# Tracking_Bug.net
KiCad netlist of a schematic drawn in EAGLE
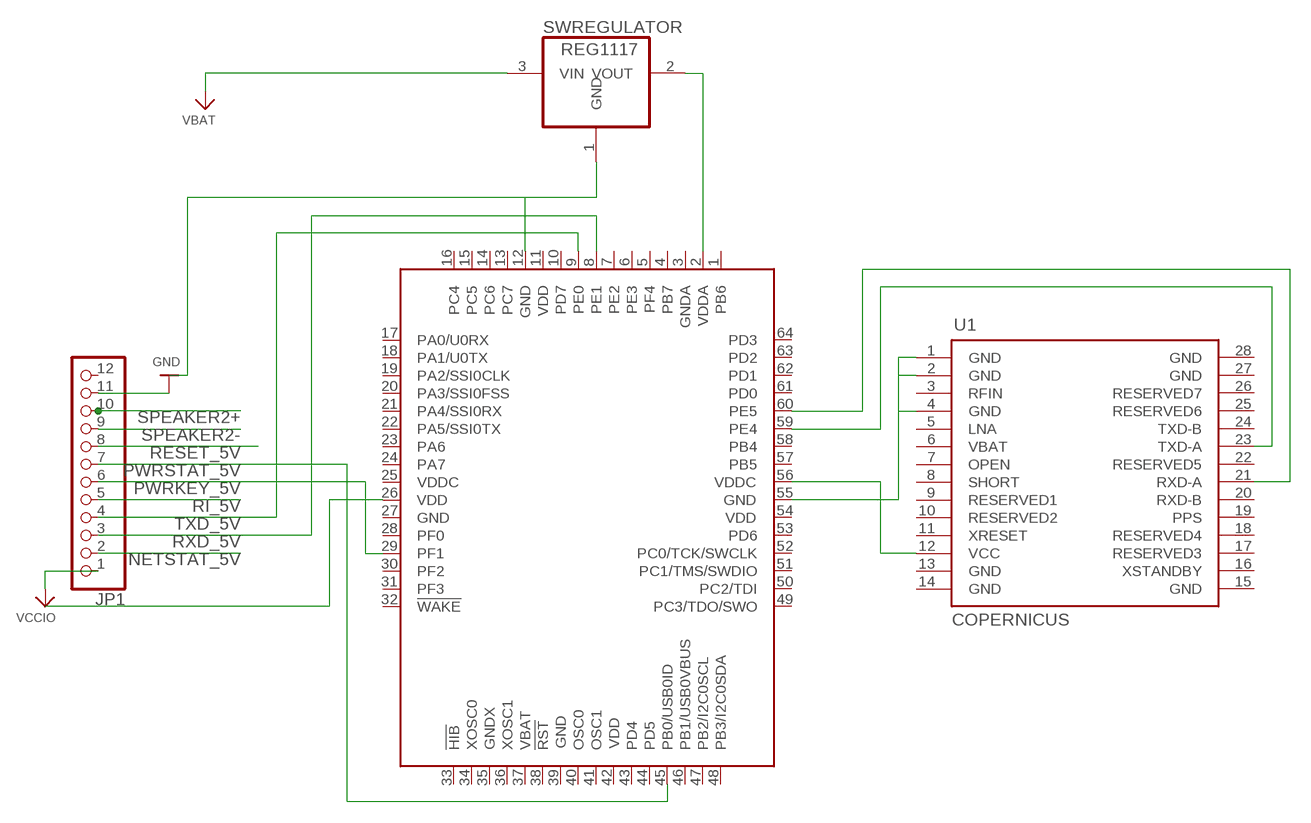
[diagram p0: schematic, sheet 1]

(export (version "E")
  (design (tool "Eeschema 10.0.6"))
  (components
    (comp (ref "IC1")
      (value "TM4C123[7,G]XXPM")
      (footprint "eagle-import:PM_S-PQFP-G64")
      (libsource (lib "eagle-import") (part "TM4C123[7,G]XXPM"))
    )
    (comp (ref "JP1")
      (value "PINHD-1X12-CB")
      (footprint "eagle-import:1X12-CB")
      (libsource (lib "eagle-import") (part "PINHD-1X12-CB"))
    )
    (comp (ref "SWREGULATOR")
      (value "REG1117")
      (footprint "eagle-import:SOT223")
      (libsource (lib "eagle-import") (part "REG1117"))
    )
    (comp (ref "U1")
      (value "COPERNICUS")
      (footprint "eagle-import:COPERNICUS")
      (libsource (lib "eagle-import") (part "COPERNICUSSMD"))
    )
  )
  (nets
    (net (code "1") (name "/NETSTAT_5V") (class "Default")
      (node (ref "JP1") (pin "2") (pinfunction "2_2") (pintype "passive"))
    )
    (net (code "2") (name "/PWRKEY_5V") (class "Default")
      (node (ref "IC1") (pin "29") (pinfunction "PF1_29") (pintype "bidirectional"))
      (node (ref "JP1") (pin "6") (pinfunction "6_6") (pintype "passive"))
    )
    (net (code "3") (name "/PWRSTAT_5V") (class "Default")
      (node (ref "IC1") (pin "45") (pinfunction "PB0/USB0ID_45") (pintype "bidirectional"))
      (node (ref "JP1") (pin "7") (pinfunction "7_7") (pintype "passive"))
    )
    (net (code "4") (name "/RESET_5V") (class "Default")
      (node (ref "JP1") (pin "8") (pinfunction "8_8") (pintype "passive"))
    )
    (net (code "5") (name "/RI_5V") (class "Default")
      (node (ref "JP1") (pin "5") (pinfunction "5_5") (pintype "passive"))
    )
    (net (code "6") (name "/RXD_5V") (class "Default")
      (node (ref "IC1") (pin "8") (pinfunction "PE1_8") (pintype "bidirectional"))
      (node (ref "JP1") (pin "3") (pinfunction "3_3") (pintype "passive"))
    )
    (net (code "7") (name "/SPEAKER2+") (class "Default")
      (node (ref "JP1") (pin "10") (pinfunction "10_10") (pintype "passive"))
    )
    (net (code "8") (name "/SPEAKER2-") (class "Default")
      (node (ref "JP1") (pin "9") (pinfunction "9_9") (pintype "passive"))
    )
    (net (code "9") (name "/TXD_5V") (class "Default")
      (node (ref "IC1") (pin "9") (pinfunction "PE0_9") (pintype "bidirectional"))
      (node (ref "JP1") (pin "4") (pinfunction "4_4") (pintype "passive"))
    )
    (net (code "10") (name "GND") (class "Default")
      (node (ref "JP1") (pin "11") (pinfunction "11_11") (pintype "passive"))
    )
    (net (code "11") (name "Net-(IC1-GND-Pad55)") (class "Default")
      (node (ref "IC1") (pin "55") (pinfunction "GND_55") (pintype "bidirectional"))
      (node (ref "U1") (pin "1") (pinfunction "GND_1") (pintype "bidirectional"))
      (node (ref "U1") (pin "2") (pinfunction "GND_2") (pintype "bidirectional"))
      (node (ref "U1") (pin "4") (pinfunction "GND_4") (pintype "bidirectional"))
    )
    (net (code "12") (name "Net-(IC1-PE4)") (class "Default")
      (node (ref "IC1") (pin "59") (pinfunction "PE4_59") (pintype "bidirectional"))
      (node (ref "U1") (pin "23") (pinfunction "TXD-A_23") (pintype "bidirectional"))
    )
    (net (code "13") (name "Net-(IC1-PE5)") (class "Default")
      (node (ref "IC1") (pin "60") (pinfunction "PE5_60") (pintype "bidirectional"))
      (node (ref "U1") (pin "21") (pinfunction "RXD-A_21") (pintype "bidirectional"))
    )
    (net (code "14") (name "Net-(IC1-VDDA)") (class "Default")
      (node (ref "IC1") (pin "2") (pinfunction "VDDA_2") (pintype "bidirectional"))
      (node (ref "SWREGULATOR") (pin "2") (pinfunction "VOUT_2") (pintype "output"))
    )
    (net (code "15") (name "Net-(SWREGULATOR-GND)") (class "Default")
      (node (ref "IC1") (pin "12") (pinfunction "GND_12") (pintype "bidirectional"))
      (node (ref "SWREGULATOR") (pin "1") (pinfunction "GND_1") (pintype "power_in"))
    )
    (net (code "16") (name "Net-(U1-VCC)") (class "Default")
      (node (ref "IC1") (pin "56") (pinfunction "VDDC_56") (pintype "bidirectional"))
      (node (ref "U1") (pin "12") (pinfunction "VCC_12") (pintype "bidirectional"))
    )
    (net (code "17") (name "VBAT") (class "Default")
      (node (ref "SWREGULATOR") (pin "3") (pinfunction "VIN_3") (pintype "input"))
    )
    (net (code "18") (name "VCCIO") (class "Default")
      (node (ref "JP1") (pin "1") (pinfunction "1_1") (pintype "passive"))
    )
    (net (code "19") (name "unconnected-(IC1-GND-Pad27)") (class "Default")
      (node (ref "IC1") (pin "27") (pinfunction "GND_27") (pintype "bidirectional"))
    )
    (net (code "20") (name "unconnected-(IC1-GND-Pad39)") (class "Default")
      (node (ref "IC1") (pin "39") (pinfunction "GND_39") (pintype "bidirectional"))
    )
    (net (code "21") (name "unconnected-(IC1-GNDA-Pad3)") (class "Default")
      (node (ref "IC1") (pin "3") (pinfunction "GNDA_3") (pintype "bidirectional"))
    )
    (net (code "22") (name "unconnected-(IC1-GNDX-Pad35)") (class "Default")
      (node (ref "IC1") (pin "35") (pinfunction "GNDX_35") (pintype "bidirectional"))
    )
    (net (code "23") (name "unconnected-(IC1-OSC0-Pad40)") (class "Default")
      (node (ref "IC1") (pin "40") (pinfunction "OSC0_40") (pintype "bidirectional"))
    )
    (net (code "24") (name "unconnected-(IC1-OSC1-Pad41)") (class "Default")
      (node (ref "IC1") (pin "41") (pinfunction "OSC1_41") (pintype "bidirectional"))
    )
    (net (code "25") (name "unconnected-(IC1-PA0{slash}U0RX-Pad17)") (class "Default")
      (node (ref "IC1") (pin "17") (pinfunction "PA0/U0RX_17") (pintype "bidirectional"))
    )
    (net (code "26") (name "unconnected-(IC1-PA1{slash}U0TX-Pad18)") (class "Default")
      (node (ref "IC1") (pin "18") (pinfunction "PA1/U0TX_18") (pintype "bidirectional"))
    )
    (net (code "27") (name "unconnected-(IC1-PA2{slash}SSI0CLK-Pad19)") (class "Default")
      (node (ref "IC1") (pin "19") (pinfunction "PA2/SSI0CLK_19") (pintype "bidirectional"))
    )
    (net (code "28") (name "unconnected-(IC1-PA3{slash}SSI0FSS-Pad20)") (class "Default")
      (node (ref "IC1") (pin "20") (pinfunction "PA3/SSI0FSS_20") (pintype "bidirectional"))
    )
    (net (code "29") (name "unconnected-(IC1-PA4{slash}SSI0RX-Pad21)") (class "Default")
      (node (ref "IC1") (pin "21") (pinfunction "PA4/SSI0RX_21") (pintype "bidirectional"))
    )
    (net (code "30") (name "unconnected-(IC1-PA5{slash}SSI0TX-Pad22)") (class "Default")
      (node (ref "IC1") (pin "22") (pinfunction "PA5/SSI0TX_22") (pintype "bidirectional"))
    )
    (net (code "31") (name "unconnected-(IC1-PA6-Pad23)") (class "Default")
      (node (ref "IC1") (pin "23") (pinfunction "PA6_23") (pintype "bidirectional"))
    )
    (net (code "32") (name "unconnected-(IC1-PA7-Pad24)") (class "Default")
      (node (ref "IC1") (pin "24") (pinfunction "PA7_24") (pintype "bidirectional"))
    )
    (net (code "33") (name "unconnected-(IC1-PB1{slash}USB0VBUS-Pad46)") (class "Default")
      (node (ref "IC1") (pin "46") (pinfunction "PB1/USB0VBUS_46") (pintype "bidirectional"))
    )
    (net (code "34") (name "unconnected-(IC1-PB2{slash}I2C0SCL-Pad47)") (class "Default")
      (node (ref "IC1") (pin "47") (pinfunction "PB2/I2C0SCL_47") (pintype "bidirectional"))
    )
    (net (code "35") (name "unconnected-(IC1-PB3{slash}I2C0SDA-Pad48)") (class "Default")
      (node (ref "IC1") (pin "48") (pinfunction "PB3/I2C0SDA_48") (pintype "bidirectional"))
    )
    (net (code "36") (name "unconnected-(IC1-PB4-Pad58)") (class "Default")
      (node (ref "IC1") (pin "58") (pinfunction "PB4_58") (pintype "bidirectional"))
    )
    (net (code "37") (name "unconnected-(IC1-PB5-Pad57)") (class "Default")
      (node (ref "IC1") (pin "57") (pinfunction "PB5_57") (pintype "bidirectional"))
    )
    (net (code "38") (name "unconnected-(IC1-PB6-Pad1)") (class "Default")
      (node (ref "IC1") (pin "1") (pinfunction "PB6_1") (pintype "bidirectional"))
    )
    (net (code "39") (name "unconnected-(IC1-PB7-Pad4)") (class "Default")
      (node (ref "IC1") (pin "4") (pinfunction "PB7_4") (pintype "bidirectional"))
    )
    (net (code "40") (name "unconnected-(IC1-PC0{slash}TCK{slash}SWCLK-Pad52)") (class "Default")
      (node (ref "IC1") (pin "52") (pinfunction "PC0/TCK/SWCLK_52") (pintype "bidirectional"))
    )
    (net (code "41") (name "unconnected-(IC1-PC1{slash}TMS{slash}SWDIO-Pad51)") (class "Default")
      (node (ref "IC1") (pin "51") (pinfunction "PC1/TMS/SWDIO_51") (pintype "bidirectional"))
    )
    (net (code "42") (name "unconnected-(IC1-PC2{slash}TDI-Pad50)") (class "Default")
      (node (ref "IC1") (pin "50") (pinfunction "PC2/TDI_50") (pintype "bidirectional"))
    )
    (net (code "43") (name "unconnected-(IC1-PC3{slash}TDO{slash}SWO-Pad49)") (class "Default")
      (node (ref "IC1") (pin "49") (pinfunction "PC3/TDO/SWO_49") (pintype "bidirectional"))
    )
    (net (code "44") (name "unconnected-(IC1-PC4-Pad16)") (class "Default")
      (node (ref "IC1") (pin "16") (pinfunction "PC4_16") (pintype "bidirectional"))
    )
    (net (code "45") (name "unconnected-(IC1-PC5-Pad15)") (class "Default")
      (node (ref "IC1") (pin "15") (pinfunction "PC5_15") (pintype "bidirectional"))
    )
    (net (code "46") (name "unconnected-(IC1-PC6-Pad14)") (class "Default")
      (node (ref "IC1") (pin "14") (pinfunction "PC6_14") (pintype "bidirectional"))
    )
    (net (code "47") (name "unconnected-(IC1-PC7-Pad13)") (class "Default")
      (node (ref "IC1") (pin "13") (pinfunction "PC7_13") (pintype "bidirectional"))
    )
    (net (code "48") (name "unconnected-(IC1-PD0-Pad61)") (class "Default")
      (node (ref "IC1") (pin "61") (pinfunction "PD0_61") (pintype "bidirectional"))
    )
    (net (code "49") (name "unconnected-(IC1-PD1-Pad62)") (class "Default")
      (node (ref "IC1") (pin "62") (pinfunction "PD1_62") (pintype "bidirectional"))
    )
    (net (code "50") (name "unconnected-(IC1-PD2-Pad63)") (class "Default")
      (node (ref "IC1") (pin "63") (pinfunction "PD2_63") (pintype "bidirectional"))
    )
    (net (code "51") (name "unconnected-(IC1-PD3-Pad64)") (class "Default")
      (node (ref "IC1") (pin "64") (pinfunction "PD3_64") (pintype "bidirectional"))
    )
    (net (code "52") (name "unconnected-(IC1-PD4-Pad43)") (class "Default")
      (node (ref "IC1") (pin "43") (pinfunction "PD4_43") (pintype "bidirectional"))
    )
    (net (code "53") (name "unconnected-(IC1-PD5-Pad44)") (class "Default")
      (node (ref "IC1") (pin "44") (pinfunction "PD5_44") (pintype "bidirectional"))
    )
    (net (code "54") (name "unconnected-(IC1-PD6-Pad53)") (class "Default")
      (node (ref "IC1") (pin "53") (pinfunction "PD6_53") (pintype "bidirectional"))
    )
    (net (code "55") (name "unconnected-(IC1-PD7-Pad10)") (class "Default")
      (node (ref "IC1") (pin "10") (pinfunction "PD7_10") (pintype "bidirectional"))
    )
    (net (code "56") (name "unconnected-(IC1-PE2-Pad7)") (class "Default")
      (node (ref "IC1") (pin "7") (pinfunction "PE2_7") (pintype "bidirectional"))
    )
    (net (code "57") (name "unconnected-(IC1-PE3-Pad6)") (class "Default")
      (node (ref "IC1") (pin "6") (pinfunction "PE3_6") (pintype "bidirectional"))
    )
    (net (code "58") (name "unconnected-(IC1-PF0-Pad28)") (class "Default")
      (node (ref "IC1") (pin "28") (pinfunction "PF0_28") (pintype "bidirectional"))
    )
    (net (code "59") (name "unconnected-(IC1-PF2-Pad30)") (class "Default")
      (node (ref "IC1") (pin "30") (pinfunction "PF2_30") (pintype "bidirectional"))
    )
    (net (code "60") (name "unconnected-(IC1-PF3-Pad31)") (class "Default")
      (node (ref "IC1") (pin "31") (pinfunction "PF3_31") (pintype "bidirectional"))
    )
    (net (code "61") (name "unconnected-(IC1-PF4-Pad5)") (class "Default")
      (node (ref "IC1") (pin "5") (pinfunction "PF4_5") (pintype "bidirectional"))
    )
    (net (code "62") (name "unconnected-(IC1-VBAT-Pad37)") (class "Default")
      (node (ref "IC1") (pin "37") (pinfunction "VBAT_37") (pintype "bidirectional"))
    )
    (net (code "63") (name "unconnected-(IC1-VDD-Pad11)") (class "Default")
      (node (ref "IC1") (pin "11") (pinfunction "VDD_11") (pintype "bidirectional"))
    )
    (net (code "64") (name "unconnected-(IC1-VDD-Pad26)") (class "Default")
      (node (ref "IC1") (pin "26") (pinfunction "VDD_26") (pintype "bidirectional"))
    )
    (net (code "65") (name "unconnected-(IC1-VDD-Pad42)") (class "Default")
      (node (ref "IC1") (pin "42") (pinfunction "VDD_42") (pintype "bidirectional"))
    )
    (net (code "66") (name "unconnected-(IC1-VDD-Pad54)") (class "Default")
      (node (ref "IC1") (pin "54") (pinfunction "VDD_54") (pintype "bidirectional"))
    )
    (net (code "67") (name "unconnected-(IC1-VDDC-Pad25)") (class "Default")
      (node (ref "IC1") (pin "25") (pinfunction "VDDC_25") (pintype "bidirectional"))
    )
    (net (code "68") (name "unconnected-(IC1-XOSC0-Pad34)") (class "Default")
      (node (ref "IC1") (pin "34") (pinfunction "XOSC0_34") (pintype "bidirectional"))
    )
    (net (code "69") (name "unconnected-(IC1-XOSC1-Pad36)") (class "Default")
      (node (ref "IC1") (pin "36") (pinfunction "XOSC1_36") (pintype "bidirectional"))
    )
    (net (code "70") (name "unconnected-(IC1-~{HIB}-Pad33)") (class "Default")
      (node (ref "IC1") (pin "33") (pinfunction "~{HIB}_33") (pintype "bidirectional"))
    )
    (net (code "71") (name "unconnected-(IC1-~{RST}-Pad38)") (class "Default")
      (node (ref "IC1") (pin "38") (pinfunction "~{RST}_38") (pintype "bidirectional"))
    )
    (net (code "72") (name "unconnected-(IC1-~{WAKE}-Pad32)") (class "Default")
      (node (ref "IC1") (pin "32") (pinfunction "~{WAKE}_32") (pintype "bidirectional"))
    )
    (net (code "73") (name "unconnected-(JP1-Pad12)") (class "Default")
      (node (ref "JP1") (pin "12") (pinfunction "12_12") (pintype "passive"))
    )
    (net (code "74") (name "unconnected-(U1-GND-Pad13)") (class "Default")
      (node (ref "U1") (pin "13") (pinfunction "GND_13") (pintype "bidirectional"))
    )
    (net (code "75") (name "unconnected-(U1-GND-Pad14)") (class "Default")
      (node (ref "U1") (pin "14") (pinfunction "GND_14") (pintype "bidirectional"))
    )
    (net (code "76") (name "unconnected-(U1-GND-Pad15)") (class "Default")
      (node (ref "U1") (pin "15") (pinfunction "GND_15") (pintype "bidirectional"))
    )
    (net (code "77") (name "unconnected-(U1-GND-Pad27)") (class "Default")
      (node (ref "U1") (pin "27") (pinfunction "GND_27") (pintype "bidirectional"))
    )
    (net (code "78") (name "unconnected-(U1-GND-Pad28)") (class "Default")
      (node (ref "U1") (pin "28") (pinfunction "GND_28") (pintype "bidirectional"))
    )
    (net (code "79") (name "unconnected-(U1-LNA-Pad5)") (class "Default")
      (node (ref "U1") (pin "5") (pinfunction "LNA_5") (pintype "bidirectional"))
    )
    (net (code "80") (name "unconnected-(U1-OPEN-Pad7)") (class "Default")
      (node (ref "U1") (pin "7") (pinfunction "OPEN_7") (pintype "bidirectional"))
    )
    (net (code "81") (name "unconnected-(U1-PPS-Pad19)") (class "Default")
      (node (ref "U1") (pin "19") (pinfunction "PPS_19") (pintype "bidirectional"))
    )
    (net (code "82") (name "unconnected-(U1-RESERVED1-Pad9)") (class "Default")
      (node (ref "U1") (pin "9") (pinfunction "RESERVED1_9") (pintype "bidirectional"))
    )
    (net (code "83") (name "unconnected-(U1-RESERVED2-Pad10)") (class "Default")
      (node (ref "U1") (pin "10") (pinfunction "RESERVED2_10") (pintype "bidirectional"))
    )
    (net (code "84") (name "unconnected-(U1-RESERVED3-Pad17)") (class "Default")
      (node (ref "U1") (pin "17") (pinfunction "RESERVED3_17") (pintype "bidirectional"))
    )
    (net (code "85") (name "unconnected-(U1-RESERVED4-Pad18)") (class "Default")
      (node (ref "U1") (pin "18") (pinfunction "RESERVED4_18") (pintype "bidirectional"))
    )
    (net (code "86") (name "unconnected-(U1-RESERVED5-Pad22)") (class "Default")
      (node (ref "U1") (pin "22") (pinfunction "RESERVED5_22") (pintype "bidirectional"))
    )
    (net (code "87") (name "unconnected-(U1-RESERVED6-Pad25)") (class "Default")
      (node (ref "U1") (pin "25") (pinfunction "RESERVED6_25") (pintype "bidirectional"))
    )
    (net (code "88") (name "unconnected-(U1-RESERVED7-Pad26)") (class "Default")
      (node (ref "U1") (pin "26") (pinfunction "RESERVED7_26") (pintype "bidirectional"))
    )
    (net (code "89") (name "unconnected-(U1-RFIN-Pad3)") (class "Default")
      (node (ref "U1") (pin "3") (pinfunction "RFIN_3") (pintype "bidirectional"))
    )
    (net (code "90") (name "unconnected-(U1-RXD-B-Pad20)") (class "Default")
      (node (ref "U1") (pin "20") (pinfunction "RXD-B_20") (pintype "bidirectional"))
    )
    (net (code "91") (name "unconnected-(U1-SHORT-Pad8)") (class "Default")
      (node (ref "U1") (pin "8") (pinfunction "SHORT_8") (pintype "bidirectional"))
    )
    (net (code "92") (name "unconnected-(U1-TXD-B-Pad24)") (class "Default")
      (node (ref "U1") (pin "24") (pinfunction "TXD-B_24") (pintype "bidirectional"))
    )
    (net (code "93") (name "unconnected-(U1-VBAT-Pad6)") (class "Default")
      (node (ref "U1") (pin "6") (pinfunction "VBAT_6") (pintype "bidirectional"))
    )
    (net (code "94") (name "unconnected-(U1-XRESET-Pad11)") (class "Default")
      (node (ref "U1") (pin "11") (pinfunction "XRESET_11") (pintype "bidirectional"))
    )
    (net (code "95") (name "unconnected-(U1-XSTANDBY-Pad16)") (class "Default")
      (node (ref "U1") (pin "16") (pinfunction "XSTANDBY_16") (pintype "bidirectional"))
    )
  )
)
